# PA.net
KiCad netlist of a schematic drawn in Altium Designer
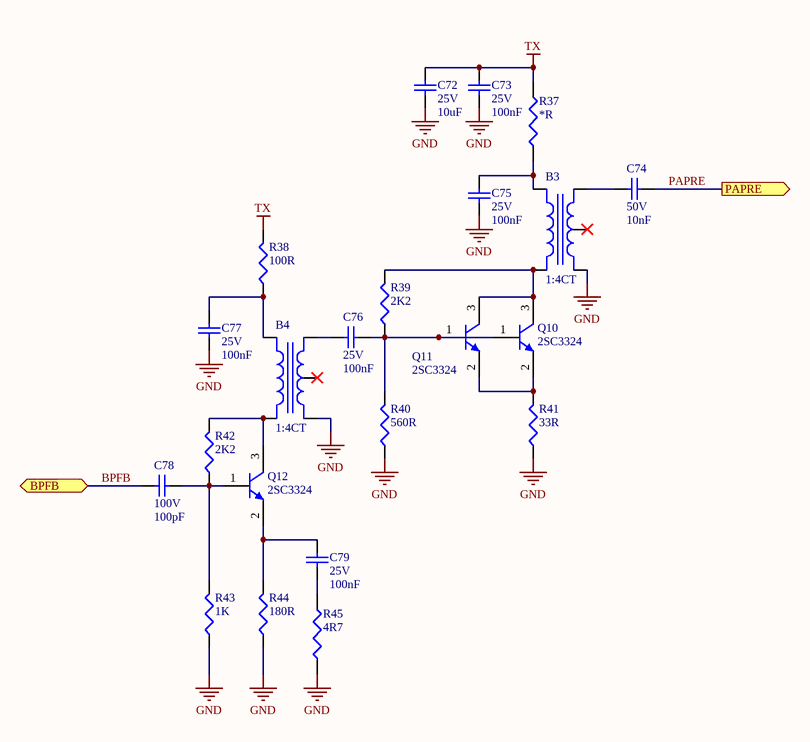
[diagram p0: PA.SchDoc]

(export (version "E")
  (design (tool "Eeschema 10.0.6"))
  (components
    (comp (ref "B3")
      (value "1:4CT")
      (footprint "CX2047LANL")
      (description "Balun 4CT:1")
      (libsource (lib "NavarroIND") (part "BALUN CX2047LANL"))
    )
    (comp (ref "B4")
      (value "1:4CT")
      (footprint "CX2047LANL")
      (description "Balun 4CT:1")
      (libsource (lib "NavarroIND") (part "BALUN CX2047LANL"))
    )
    (comp (ref "C72")
      (value "10uF")
      (footprint "CC0805")
      (description "Capacitor (Semiconductor SIM Model)")
      (fields (field (name "TENSÃO") "25V") (field (name "Comment") "Capacitor Cerâmico"))
      (libsource (lib "NavarroCAP") (part "Cap 10uF 25V 0805 X5R"))
    )
    (comp (ref "C73")
      (value "100nF")
      (footprint "CC0603")
      (description "Capacitor (Semiconductor SIM Model)")
      (fields (field (name "TENSÃO") "25V") (field (name "Comment") "Capacitor Cerâmico"))
      (libsource (lib "NavarroCAP") (part "Cap 100nF 25V 0603 X7R"))
    )
    (comp (ref "C74")
      (value "10nF")
      (footprint "CC0603")
      (description "Capacitor (Semiconductor SIM Model)")
      (fields (field (name "TENSÃO") "50V") (field (name "Comment") "Capacitor Cerâmico"))
      (libsource (lib "NavarroCAP") (part "Cap 10nF 50V 0603 X7R 5%"))
    )
    (comp (ref "C75")
      (value "100nF")
      (footprint "CC0603")
      (description "Capacitor (Semiconductor SIM Model)")
      (fields (field (name "TENSÃO") "25V") (field (name "Comment") "Capacitor Cerâmico"))
      (libsource (lib "NavarroCAP") (part "Cap 100nF 25V 0603 X7R"))
    )
    (comp (ref "C76")
      (value "100nF")
      (footprint "CC0603")
      (description "Capacitor (Semiconductor SIM Model)")
      (fields (field (name "TENSÃO") "25V") (field (name "Comment") "Capacitor Cerâmico"))
      (libsource (lib "NavarroCAP") (part "Cap 100nF 25V 0603 X7R"))
    )
    (comp (ref "C77")
      (value "100nF")
      (footprint "CC0603")
      (description "Capacitor (Semiconductor SIM Model)")
      (fields (field (name "TENSÃO") "25V") (field (name "Comment") "Capacitor Cerâmico"))
      (libsource (lib "NavarroCAP") (part "Cap 100nF 25V 0603 X7R"))
    )
    (comp (ref "C78")
      (value "100pF")
      (footprint "CC0603")
      (description "Capacitor (Semiconductor SIM Model)")
      (fields (field (name "TENSÃO") "100V") (field (name "Comment") "Capacitor Cerâmico"))
      (libsource (lib "NavarroCAP") (part "Cap 100pF 100V 0603 NP0"))
    )
    (comp (ref "C79")
      (value "100nF")
      (footprint "CC0603")
      (description "Capacitor (Semiconductor SIM Model)")
      (fields (field (name "TENSÃO") "25V") (field (name "Comment") "Capacitor Cerâmico"))
      (libsource (lib "NavarroCAP") (part "Cap 100nF 25V 0603 X7R"))
    )
    (comp (ref "Q10")
      (value "2SC3324")
      (footprint "SOT-23-3N")
      (description "NPN General Purpose Amplifier")
      (libsource (lib "NavarroSEMI") (part "TRS 2SC3324 120V 100mA SOT-23-3"))
    )
    (comp (ref "Q11")
      (value "2SC3324")
      (footprint "SOT-23-3N")
      (description "NPN General Purpose Amplifier")
      (libsource (lib "NavarroSEMI") (part "TRS 2SC3324 120V 100mA SOT-23-3"))
    )
    (comp (ref "Q12")
      (value "2SC3324")
      (footprint "SOT-23-3N")
      (description "NPN General Purpose Amplifier")
      (libsource (lib "NavarroSEMI") (part "TRS 2SC3324 120V 100mA SOT-23-3"))
    )
    (comp (ref "R37")
      (value "*R")
      (footprint "CC0603")
      (description "Resistor")
      (libsource (lib "NavarroRES") (part "Res - $Val $% $Footprint $Pot"))
    )
    (comp (ref "R38")
      (value "100R")
      (footprint "CC0603")
      (description "Resistor")
      (libsource (lib "NavarroRES") (part "Res 100R 5% 0603 1/10W"))
    )
    (comp (ref "R39")
      (value "2K2")
      (footprint "CC0603")
      (description "Resistor")
      (libsource (lib "NavarroRES") (part "Res 2K2 5% 0603 1/10W"))
    )
    (comp (ref "R40")
      (value "560R")
      (footprint "CC0306")
      (description "Resistor")
      (libsource (lib "NavarroRES") (part "Res 560R 1% 0603 1/8W"))
    )
    (comp (ref "R41")
      (value "33R")
      (footprint "CC0603")
      (description "Resistor")
      (libsource (lib "NavarroRES") (part "Res 33R 1% 0603 1/10W"))
    )
    (comp (ref "R42")
      (value "2K2")
      (footprint "CC0603")
      (description "Resistor")
      (libsource (lib "NavarroRES") (part "Res 2K2 5% 0603 1/10W"))
    )
    (comp (ref "R43")
      (value "1K")
      (footprint "CC0603")
      (description "Resistor")
      (libsource (lib "NavarroRES") (part "Res 1K 1% 0603 1/10W"))
    )
    (comp (ref "R44")
      (value "180R")
      (footprint "CC0603")
      (description "Resistor")
      (libsource (lib "NavarroRES") (part "Res 180R 1% 0603 1/10W"))
    )
    (comp (ref "R45")
      (value "4R7")
      (footprint "CC0603")
      (description "Resistor")
      (libsource (lib "NavarroRES") (part "Res 4R7 1% 0603 1/10W"))
    )
  )
  (nets
    (net (code "1") (name "/BPFB") (class "Default")
      (node (ref "C78") (pin "1") (pinfunction "1_1") (pintype "passive"))
    )
    (net (code "2") (name "/PAPRE") (class "Default")
      (node (ref "C74") (pin "1") (pinfunction "1_1") (pintype "passive"))
    )
    (net (code "3") (name "GND") (class "Default")
      (node (ref "B3") (pin "3") (pinfunction "Pri-_3") (pintype "passive"))
      (node (ref "B4") (pin "3") (pinfunction "Pri-_3") (pintype "passive"))
      (node (ref "C72") (pin "1") (pinfunction "1_1") (pintype "passive"))
      (node (ref "C73") (pin "2") (pinfunction "2_2") (pintype "passive"))
      (node (ref "C75") (pin "2") (pinfunction "2_2") (pintype "passive"))
      (node (ref "C77") (pin "1") (pinfunction "1_1") (pintype "passive"))
      (node (ref "R40") (pin "1") (pinfunction "1_1") (pintype "passive"))
      (node (ref "R41") (pin "1") (pinfunction "1_1") (pintype "passive"))
      (node (ref "R43") (pin "1") (pinfunction "1_1") (pintype "passive"))
      (node (ref "R44") (pin "1") (pinfunction "1_1") (pintype "passive"))
      (node (ref "R45") (pin "1") (pinfunction "1_1") (pintype "passive"))
    )
    (net (code "4") (name "Net-(B3-Pri+)") (class "Default")
      (node (ref "B3") (pin "4") (pinfunction "Pri+_4") (pintype "passive"))
      (node (ref "Q10") (pin "3") (pinfunction "C_3") (pintype "passive"))
      (node (ref "Q11") (pin "3") (pinfunction "C_3") (pintype "passive"))
      (node (ref "R39") (pin "2") (pinfunction "2_2") (pintype "passive"))
    )
    (net (code "5") (name "Net-(B3-Sec+-Pad1)") (class "Default")
      (node (ref "B3") (pin "1") (pinfunction "Sec+_1") (pintype "passive"))
      (node (ref "C74") (pin "2") (pinfunction "2_2") (pintype "passive"))
    )
    (net (code "6") (name "Net-(B3-Sec-)") (class "Default")
      (node (ref "B3") (pin "6") (pinfunction "Sec-_6") (pintype "passive"))
      (node (ref "C75") (pin "1") (pinfunction "1_1") (pintype "passive"))
      (node (ref "R37") (pin "1") (pinfunction "1_1") (pintype "passive"))
    )
    (net (code "7") (name "Net-(B4-Pri+)") (class "Default")
      (node (ref "B4") (pin "4") (pinfunction "Pri+_4") (pintype "passive"))
      (node (ref "Q12") (pin "3") (pinfunction "C_3") (pintype "passive"))
      (node (ref "R42") (pin "2") (pinfunction "2_2") (pintype "passive"))
    )
    (net (code "8") (name "Net-(B4-Sec+-Pad1)") (class "Default")
      (node (ref "B4") (pin "1") (pinfunction "Sec+_1") (pintype "passive"))
      (node (ref "C76") (pin "2") (pinfunction "2_2") (pintype "passive"))
    )
    (net (code "9") (name "Net-(B4-Sec-)") (class "Default")
      (node (ref "B4") (pin "6") (pinfunction "Sec-_6") (pintype "passive"))
      (node (ref "C77") (pin "2") (pinfunction "2_2") (pintype "passive"))
      (node (ref "R38") (pin "1") (pinfunction "1_1") (pintype "passive"))
    )
    (net (code "10") (name "Net-(C79-Pad1)") (class "Default")
      (node (ref "C79") (pin "1") (pinfunction "1_1") (pintype "passive"))
      (node (ref "R45") (pin "2") (pinfunction "2_2") (pintype "passive"))
    )
    (net (code "11") (name "Net-(Q10-B)") (class "Default")
      (node (ref "C76") (pin "1") (pinfunction "1_1") (pintype "passive"))
      (node (ref "Q10") (pin "1") (pinfunction "B_1") (pintype "passive"))
      (node (ref "Q11") (pin "1") (pinfunction "B_1") (pintype "passive"))
      (node (ref "R39") (pin "1") (pinfunction "1_1") (pintype "passive"))
      (node (ref "R40") (pin "2") (pinfunction "2_2") (pintype "passive"))
    )
    (net (code "12") (name "Net-(Q10-E)") (class "Default")
      (node (ref "Q10") (pin "2") (pinfunction "E_2") (pintype "passive"))
      (node (ref "Q11") (pin "2") (pinfunction "E_2") (pintype "passive"))
      (node (ref "R41") (pin "2") (pinfunction "2_2") (pintype "passive"))
    )
    (net (code "13") (name "Net-(Q12-B)") (class "Default")
      (node (ref "C78") (pin "2") (pinfunction "2_2") (pintype "passive"))
      (node (ref "Q12") (pin "1") (pinfunction "B_1") (pintype "passive"))
      (node (ref "R42") (pin "1") (pinfunction "1_1") (pintype "passive"))
      (node (ref "R43") (pin "2") (pinfunction "2_2") (pintype "passive"))
    )
    (net (code "14") (name "Net-(Q12-E)") (class "Default")
      (node (ref "C79") (pin "2") (pinfunction "2_2") (pintype "passive"))
      (node (ref "Q12") (pin "2") (pinfunction "E_2") (pintype "passive"))
      (node (ref "R44") (pin "2") (pinfunction "2_2") (pintype "passive"))
    )
    (net (code "15") (name "TX") (class "Default")
      (node (ref "C72") (pin "2") (pinfunction "2_2") (pintype "passive"))
      (node (ref "C73") (pin "1") (pinfunction "1_1") (pintype "passive"))
      (node (ref "R37") (pin "2") (pinfunction "2_2") (pintype "passive"))
      (node (ref "R38") (pin "2") (pinfunction "2_2") (pintype "passive"))
    )
    (net (code "16") (name "unconnected-(B3-Sec+-Pad2)") (class "Default")
      (node (ref "B3") (pin "2") (pinfunction "Sec+_2") (pintype "passive+no_connect"))
    )
    (net (code "17") (name "unconnected-(B4-Sec+-Pad2)") (class "Default")
      (node (ref "B4") (pin "2") (pinfunction "Sec+_2") (pintype "passive+no_connect"))
    )
  )
)
